# v1_0.net
KiCad netlist of a schematic drawn in Altium Designer
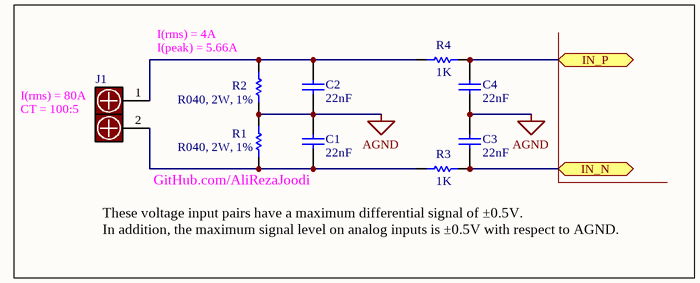
[diagram p0: v1.0.SchDoc]

(export (version "E")
  (design (tool "Eeschema 10.0.6"))
  (components
    (comp (ref "C1")
      (value "22nF")
      (footprint "Capacitor_Ceramic:SMD_0805")
      (description "Capacitor, Ceramic Multilayer")
      (libsource (lib "General") (part "Capacitor_Ceramic"))
    )
    (comp (ref "C2")
      (value "22nF")
      (footprint "Capacitor_Ceramic:SMD_0805")
      (description "Capacitor, Ceramic Multilayer")
      (libsource (lib "General") (part "Capacitor_Ceramic"))
    )
    (comp (ref "C3")
      (value "22nF")
      (footprint "Capacitor_Ceramic:SMD_0805")
      (description "Capacitor, Ceramic Multilayer")
      (libsource (lib "General") (part "Capacitor_Ceramic"))
    )
    (comp (ref "C4")
      (value "22nF")
      (footprint "Capacitor_Ceramic:SMD_0805")
      (description "Capacitor, Ceramic Multilayer")
      (libsource (lib "General") (part "Capacitor_Ceramic"))
    )
    (comp (ref "J1")
      (value "~")
      (footprint "1x2_P8.26")
      (description "Connector, Barrier Terminal Blocks, 2Pin")
      (libsource (lib "Connector") (part "Connector1x2_Power_4Form"))
    )
    (comp (ref "R1")
      (value "R040, 2W, 1%")
      (footprint "SMD_4527")
      (description "Resistor, 2W, 1%")
      (libsource (lib "") (part "Resistor_1"))
    )
    (comp (ref "R2")
      (value "R040, 2W, 1%")
      (footprint "SMD_4527")
      (description "Resistor, 2W, 1%")
      (libsource (lib "") (part "Resistor_1"))
    )
    (comp (ref "R3")
      (value "1K")
      (footprint "SMD_0805")
      (description "Resistor, 1/8W")
      (libsource (lib "General") (part "Resistor"))
    )
    (comp (ref "R4")
      (value "1K")
      (footprint "SMD_0805")
      (description "Resistor, 1/8W")
      (libsource (lib "General") (part "Resistor"))
    )
  )
  (nets
    (net (code "1") (name "/IN_N") (class "Default")
      (node (ref "C3") (pin "2") (pinfunction "2_2") (pintype "passive"))
      (node (ref "R3") (pin "1") (pinfunction "1_1") (pintype "passive"))
    )
    (net (code "2") (name "/IN_P") (class "Default")
      (node (ref "C4") (pin "1") (pinfunction "1_1") (pintype "passive"))
      (node (ref "R4") (pin "1") (pinfunction "1_1") (pintype "passive"))
    )
    (net (code "3") (name "AGND") (class "Default")
      (node (ref "C1") (pin "1") (pinfunction "1_1") (pintype "passive"))
      (node (ref "C2") (pin "2") (pinfunction "2_2") (pintype "passive"))
      (node (ref "C3") (pin "1") (pinfunction "1_1") (pintype "passive"))
      (node (ref "C4") (pin "2") (pinfunction "2_2") (pintype "passive"))
      (node (ref "R1") (pin "2") (pinfunction "2_2") (pintype "passive"))
      (node (ref "R2") (pin "1") (pinfunction "1_1") (pintype "passive"))
    )
    (net (code "4") (name "Net-(C1-Pad2)") (class "Default")
      (node (ref "C1") (pin "2") (pinfunction "2_2") (pintype "passive"))
      (node (ref "J1") (pin "2") (pinfunction "2_2") (pintype "passive"))
      (node (ref "R1") (pin "1") (pinfunction "1_1") (pintype "passive"))
      (node (ref "R3") (pin "2") (pinfunction "2_2") (pintype "passive"))
    )
    (net (code "5") (name "Net-(C2-Pad1)") (class "Default")
      (node (ref "C2") (pin "1") (pinfunction "1_1") (pintype "passive"))
      (node (ref "J1") (pin "1") (pinfunction "1_1") (pintype "passive"))
      (node (ref "R2") (pin "2") (pinfunction "2_2") (pintype "passive"))
      (node (ref "R4") (pin "2") (pinfunction "2_2") (pintype "passive"))
    )
  )
)
